# CH570Q-UART-R0.net
KiCad netlist of a schematic drawn in Altium Designer
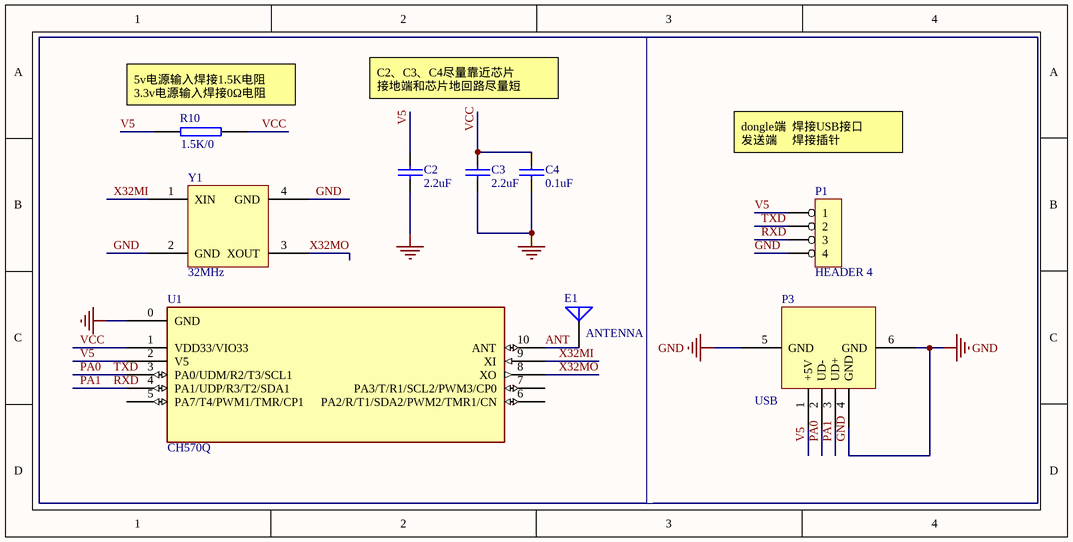
[diagram p0: CH570Q-UART-R0.SchDoc]

(export (version "E")
  (design (tool "Eeschema 10.0.6"))
  (components
    (comp (ref "C2")
      (value "2.2uF")
      (footprint "0402_C")
      (description "Capacitor")
      (libsource (lib "*") (part "CAP"))
    )
    (comp (ref "C3")
      (value "2.2uF")
      (footprint "0402_C")
      (description "Capacitor")
      (libsource (lib "*") (part "CAP"))
    )
    (comp (ref "C4")
      (value "0.1uF")
      (footprint "0402_C")
      (description "Capacitor")
      (libsource (lib "*") (part "CAP"))
    )
    (comp (ref "E1")
      (value "ANTENNA")
      (footprint "ANT-F-1-2.4G-0.8mmFR4")
      (description "Generic Antenna")
      (libsource (lib "*") (part "ANTENNA"))
    )
    (comp (ref "P1")
      (value "HEADER 4")
      (footprint "SIP4-2.54mm")
      (description "Header, 4-Pin")
      (libsource (lib "wch_sch_others") (part "HEADER 4"))
    )
    (comp (ref "P3") (value "USB") (footprint "USBAM-4P") (libsource (lib "Schlib1") (part "USB")))
    (comp (ref "R10") (value "1.5K/0") (footprint "0402") (libsource (lib "*") (part "RES2")))
    (comp (ref "U1")
      (value "CH570Q")
      (footprint "DFN10_3X3")
      (description "RISC-V MCU with BLE/2.4GHz Wireless/USB/UART/I2C/PWM/CMP")
      (libsource (lib "PCB_Project") (part "CH570Q"))
    )
    (comp (ref "Y1") (value "32MHz") (footprint "XT2016") (libsource (lib "wch_sch_others") (part "晶体")))
  )
  (nets
    (net (code "1") (name "/ANT") (class "Default")
      (node (ref "E1") (pin "1") (pinfunction "A_1") (pintype "passive"))
      (node (ref "U1") (pin "10") (pinfunction "ANT_10") (pintype "bidirectional"))
    )
    (net (code "2") (name "/PA0") (class "Default")
      (node (ref "P1") (pin "2") (pinfunction "2_2") (pintype "passive"))
      (node (ref "P3") (pin "2") (pinfunction "UD-_2") (pintype "passive"))
      (node (ref "U1") (pin "3") (pinfunction "PA0/UDM/R2/T3/SCL1_3") (pintype "bidirectional"))
    )
    (net (code "3") (name "/PA1") (class "Default")
      (node (ref "P1") (pin "3") (pinfunction "3_3") (pintype "passive"))
      (node (ref "P3") (pin "3") (pinfunction "UD+_3") (pintype "passive"))
      (node (ref "U1") (pin "4") (pinfunction "PA1/UDP/R3/T2/SDA1_4") (pintype "bidirectional"))
    )
    (net (code "4") (name "/V5") (class "Default")
      (node (ref "C2") (pin "1") (pinfunction "1_1") (pintype "passive"))
      (node (ref "P1") (pin "1") (pinfunction "1_1") (pintype "passive"))
      (node (ref "P3") (pin "1") (pinfunction "+5V_1") (pintype "passive"))
      (node (ref "R10") (pin "1") (pinfunction "1_1") (pintype "passive"))
      (node (ref "U1") (pin "2") (pinfunction "V5_2") (pintype "power_in"))
    )
    (net (code "5") (name "/VCC") (class "Default")
      (node (ref "C3") (pin "1") (pinfunction "1_1") (pintype "passive"))
      (node (ref "C4") (pin "1") (pinfunction "1_1") (pintype "passive"))
      (node (ref "R10") (pin "2") (pinfunction "2_2") (pintype "passive"))
      (node (ref "U1") (pin "1") (pinfunction "VDD33/VIO33_1") (pintype "power_in"))
    )
    (net (code "6") (name "/X32MI") (class "Default")
      (node (ref "U1") (pin "9") (pinfunction "XI_9") (pintype "input"))
      (node (ref "Y1") (pin "1") (pinfunction "XIN_1") (pintype "passive"))
    )
    (net (code "7") (name "/X32MO") (class "Default")
      (node (ref "U1") (pin "8") (pinfunction "XO_8") (pintype "output"))
      (node (ref "Y1") (pin "3") (pinfunction "XOUT_3") (pintype "passive"))
    )
    (net (code "8") (name "GND") (class "Default")
      (node (ref "C2") (pin "2") (pinfunction "2_2") (pintype "passive"))
      (node (ref "C3") (pin "2") (pinfunction "2_2") (pintype "passive"))
      (node (ref "C4") (pin "2") (pinfunction "2_2") (pintype "passive"))
      (node (ref "P1") (pin "4") (pinfunction "4_4") (pintype "passive"))
      (node (ref "P3") (pin "4") (pinfunction "GND_4") (pintype "passive"))
      (node (ref "P3") (pin "5") (pinfunction "GND_5") (pintype "passive"))
      (node (ref "P3") (pin "6") (pinfunction "GND_6") (pintype "passive"))
      (node (ref "U1") (pin "0") (pinfunction "GND_0") (pintype "power_in"))
      (node (ref "Y1") (pin "2") (pinfunction "GND_2") (pintype "passive"))
      (node (ref "Y1") (pin "4") (pinfunction "GND_4") (pintype "passive"))
    )
    (net (code "9") (name "unconnected-(U1-PA2{slash}R{slash}T1{slash}SDA2{slash}PWM2{slash}TMR1{slash}CN-Pad6)") (class "Default")
      (node (ref "U1") (pin "6") (pinfunction "PA2/R/T1/SDA2/PWM2/TMR1/CN_6") (pintype "bidirectional"))
    )
    (net (code "10") (name "unconnected-(U1-PA3{slash}T{slash}R1{slash}SCL2{slash}PWM3{slash}CP0-Pad7)") (class "Default")
      (node (ref "U1") (pin "7") (pinfunction "PA3/T/R1/SCL2/PWM3/CP0_7") (pintype "bidirectional"))
    )
    (net (code "11") (name "unconnected-(U1-PA7{slash}T4{slash}PWM1{slash}TMR{slash}CP1-Pad5)") (class "Default")
      (node (ref "U1") (pin "5") (pinfunction "PA7/T4/PWM1/TMR/CP1_5") (pintype "bidirectional"))
    )
  )
)
